# Power.net
KiCad netlist of a schematic drawn in Altium Designer
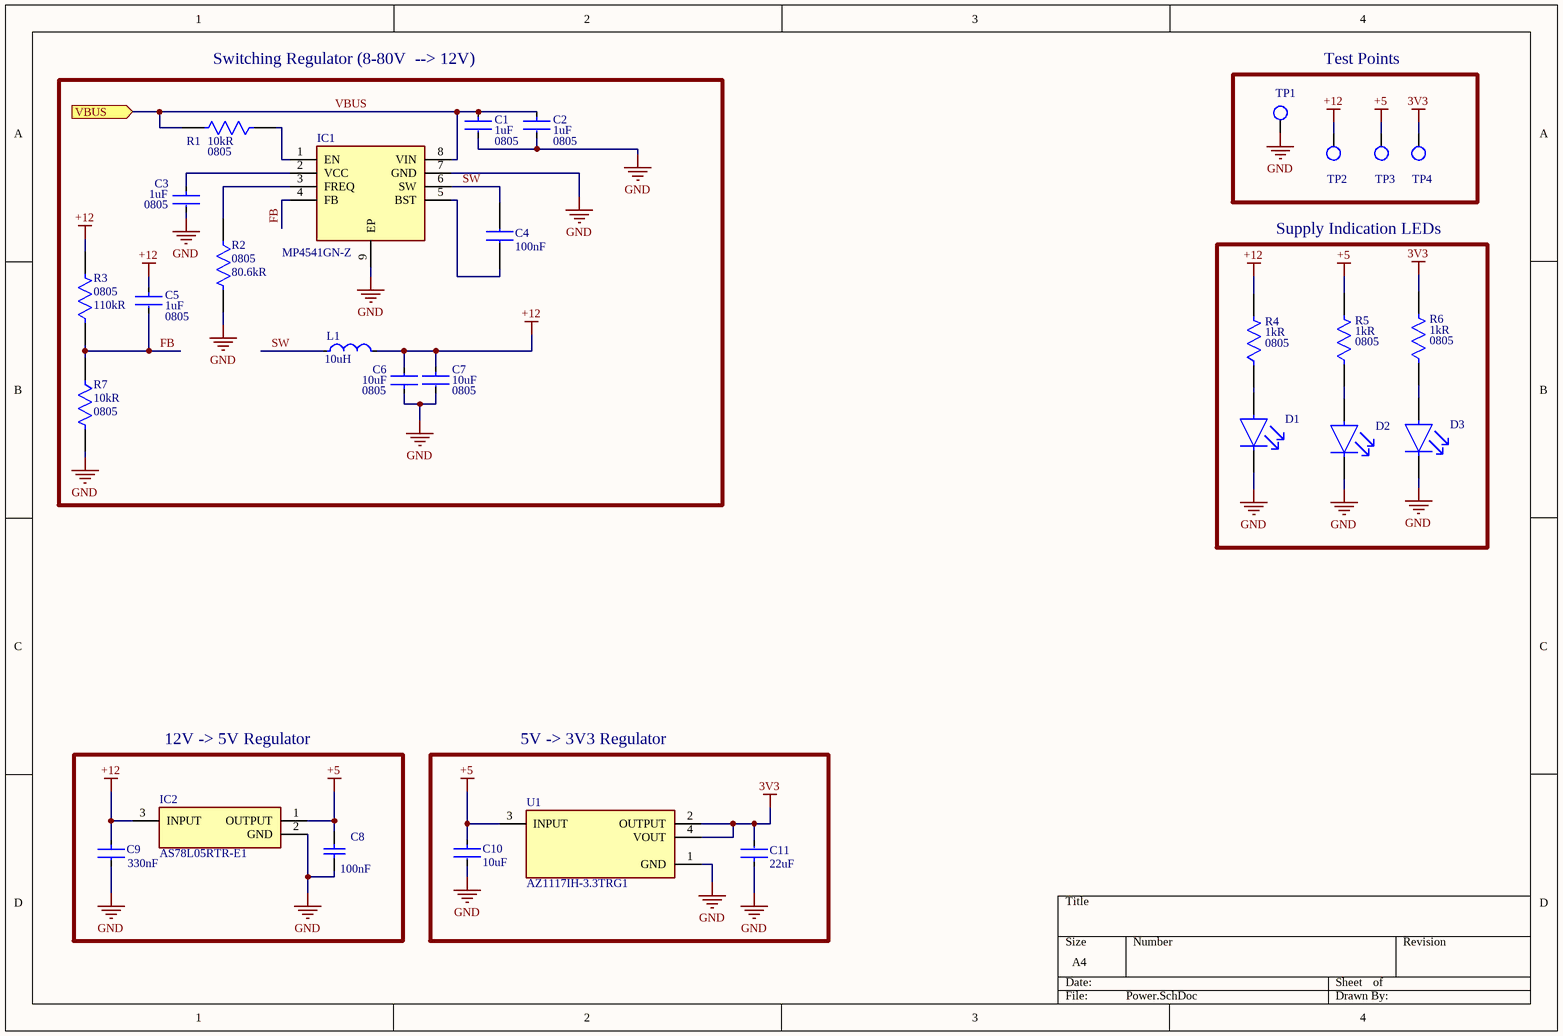
[diagram p0: Power.SchDoc]

(export (version "E")
  (design (tool "Eeschema 10.0.6"))
  (components
    (comp (ref "C1")
      (value "885012207078")
      (footprint "FP-885012207078-MFG")
      (description "CAP CER 1UF 25V X7R 0805")
      (fields
        (field (name "CAPACITANCE") "1uF")
        (field (name "CASE CODE (IMPERIAL)") "0805")
        (field (name "TOLERANCE") "10%")
      )
      (libsource (lib "Altium Content Vault") (part "b4654b650e69147ec39a6b967a45e02"))
    )
    (comp (ref "C2")
      (value "885012207078")
      (footprint "FP-885012207078-MFG")
      (description "CAP CER 1UF 25V X7R 0805")
      (fields
        (field (name "CAPACITANCE") "1uF")
        (field (name "CASE CODE (IMPERIAL)") "0805")
        (field (name "TOLERANCE") "10%")
      )
      (libsource (lib "Altium Content Vault") (part "b4654b650e69147ec39a6b967a45e02"))
    )
    (comp (ref "C3")
      (value "885012207078")
      (footprint "FP-885012207078-MFG")
      (description "CAP CER 1UF 25V X7R 0805")
      (fields
        (field (name "CAPACITANCE") "1uF")
        (field (name "CASE CODE (IMPERIAL)") "0805")
        (field (name "TOLERANCE") "10%")
      )
      (libsource (lib "Altium Content Vault") (part "b4654b650e69147ec39a6b967a45e02"))
    )
    (comp (ref "C4")
      (value "C0805C104K1RACAUTO7210")
      (footprint "C0805")
      (description "Capacitor")
      (fields (field (name "MOUSER PART NUMBER") "80-C0805C104K1RAUTLR") (field (name "CAPACITANCE") "100nF"))
      (libsource (lib "WPT_Transmitter_lib") (part "C0805C104K1RACAUTO7210"))
    )
    (comp (ref "C5")
      (value "885012207078")
      (footprint "FP-885012207078-MFG")
      (description "CAP CER 1UF 25V X7R 0805")
      (fields
        (field (name "CAPACITANCE") "1uF")
        (field (name "CASE CODE (IMPERIAL)") "0805")
        (field (name "TOLERANCE") "10%")
      )
      (libsource (lib "Altium Content Vault") (part "b4654b650e69147ec39a6b967a45e02"))
    )
    (comp (ref "C6")
      (value "CL21A106KOQNNNG")
      (footprint "FP-CL21-IPC_C")
      (description "CL21 Series 0805 10uF 16V ±10% Tolerance X5R Multilayer Ceramic Chip Capacitor")
      (fields
        (field (name "CAPACITANCE") "10uF")
        (field (name "TOLERANCE") "10%")
        (field (name "CASE/PACKAGE") "0805")
        (field (name "VOLTAGE") "16V")
      )
      (libsource (lib "Altium Content Vault") (part "b4654b650e69147ec39a6b967a45e02"))
    )
    (comp (ref "C7")
      (value "CL21A106KOQNNNG")
      (footprint "FP-CL21-IPC_C")
      (description "CL21 Series 0805 10uF 16V ±10% Tolerance X5R Multilayer Ceramic Chip Capacitor")
      (fields
        (field (name "CAPACITANCE") "10uF")
        (field (name "TOLERANCE") "10%")
        (field (name "CASE/PACKAGE") "0805")
        (field (name "VOLTAGE") "16V")
      )
      (libsource (lib "Altium Content Vault") (part "b4654b650e69147ec39a6b967a45e02"))
    )
    (comp (ref "C8")
      (value "08055D104KAT2A")
      (footprint "CAPC2013X140X50ML20T25")
      (fields (field (name "MANUFACTURER") "AVX Interconnect / Elco") (field (name "CAPACITANCE") "100nF"))
      (libsource (lib "Altium Content Vault") (part "CAP"))
    )
    (comp (ref "C9")
      (value "CL21B334KBFNNNE")
      (footprint "FP-CL21-F-IPC_C")
      (description "CAP CER 0.33UF 50V X7R 0805")
      (fields
        (field (name "CAPACITANCE") "330nF")
        (field (name "MANUFACTURER") "Samsung Electro-Mechanics")
        (field (name "OCTOPART") "https://octopart.com/cl21b334kbfnnne-samsung-9287149")
      )
      (libsource (lib "Altium Content Vault") (part "11868f565c42a9108669ba33697ecf6"))
    )
    (comp (ref "C10")
      (value "CL21A106KOQNNNE")
      (footprint "FP-CL21-IPC_B")
      (description "CL21 Series 0805 10uF 16V ±10% Tolerance X5R Multilayer Ceramic Chip Capacitor")
      (fields
        (field (name "VOLTAGE") "16V")
        (field (name "CAPACITANCE") "10uF")
        (field (name "TOLERANCE") "10%")
      )
      (libsource (lib "Altium Content Vault") (part "b4654b650e69147ec39a6b967a45e02"))
    )
    (comp (ref "C11")
      (value "CL21A226MQQNNNG")
      (footprint "FP-CL21-IPC_B")
      (description "CL21 Series 0805 22uF 6.3V ±20% Tolerance X5R Multilayer Ceramic Chip Capacitor")
      (fields
        (field (name "TOLERANCE") "20%")
        (field (name "CAPACITANCE") "22uF")
        (field (name "VOLTAGE") "6.3V")
      )
      (libsource (lib "Altium Content Vault") (part "b4654b650e69147ec39a6b967a45e02"))
    )
    (comp (ref "D1")
      (value "12V")
      (footprint "FP-150060VS75000-MFG")
      (description "LED GREEN CLEAR 0603 SMD")
      (libsource (lib "Altium Content Vault") (part "8706943c75ba83719d021d2fdc84c58"))
    )
    (comp (ref "D2")
      (value "5V")
      (footprint "FP-150060VS75000-MFG")
      (description "LED GREEN CLEAR 0603 SMD")
      (libsource (lib "Altium Content Vault") (part "8706943c75ba83719d021d2fdc84c58"))
    )
    (comp (ref "D3")
      (value "3V3")
      (footprint "FP-150060VS75000-MFG")
      (description "LED GREEN CLEAR 0603 SMD")
      (libsource (lib "Altium Content Vault") (part "8706943c75ba83719d021d2fdc84c58"))
    )
    (comp (ref "IC1")
      (value "MP4541GN-Z")
      (footprint "WPT_Transmitter_lib:SOIC127P600X170-9N")
      (description "Integrated Circuit")
      (fields (field (name "MOUSER PART NUMBER") "946-MP4541GN-Z"))
      (libsource (lib "WPT_Transmitter_lib") (part "MP4541GN-Z"))
    )
    (comp (ref "IC2")
      (value "AS78L05RTR-E1")
      (footprint "WPT_Transmitter_lib:DIODES_SOT-89")
      (description "Integrated Circuit")
      (fields (field (name "MOUSER PART NUMBER") "621-AS78L05RTR-E1"))
      (libsource (lib "WPT_Transmitter_lib") (part "AS78L05RTR-E1"))
    )
    (comp (ref "L1")
      (value "LBR2518T100K")
      (footprint "FP-LB2518-1_8-0_2-IPC_A")
      (description "SMD Inductors 10uH ±10% 0.235A 0.247Ω 1007")
      (fields (field (name "INDUCTANCE") "10uH") (field (name "TOLERANCE") "10%"))
      (libsource (lib "Altium Content Vault") (part "725321dda6339637d4d059423bc1c3c"))
    )
    (comp (ref "R1")
      (value "RMCF0805JT10K0")
      (footprint "FP-RMCF0805-IPC_A")
      (description "10kΩ ±5% 0.125W 0805 Thick Film Chip Resistor AEC-Q200 compliant")
      (fields
        (field (name "RESISTANCE") "10kR")
        (field (name "CASE CODE (IMPERIAL)") "0805")
        (field (name "TOLERANCE") "5%")
      )
      (libsource (lib "Altium Content Vault") (part "1029c3af85768c4190bb7ad29bc67b5"))
    )
    (comp (ref "R2")
      (value "CRCW080580K6FKEA")
      (footprint "FP-CRCW0805-e3-IPC_A")
      (description "RES Thick Film, 80.6kΩ, 1%, 0.125W, 100ppm/°C, 0805")
      (fields
        (field (name "TOLERANCE") "1%")
        (field (name "CASE/PACKAGE") "0805")
        (field (name "RESISTANCE") "80.6kR")
      )
      (libsource (lib "Altium Content Vault") (part "1029c3af85768c4190bb7ad29bc67b5"))
    )
    (comp (ref "R3")
      (value "RMCF0805FT110K")
      (footprint "FP-RMCF0805-IPC_C")
      (description "110kΩ ±1% 0.125W 0805 Thick Film Chip Resistor AEC-Q200 compliant")
      (fields
        (field (name "SIZE CODE") "0805")
        (field (name "TOLERANCE") "1%")
        (field (name "RESISTANCE") "110kR")
      )
      (libsource (lib "Altium Content Vault") (part "1029c3af85768c4190bb7ad29bc67b5"))
    )
    (comp (ref "R4")
      (value "RNCP0805FTD1K00")
      (footprint "FP-RNCP0805-MFG")
      (description "1kΩ ±1% 0.25W 0805 High Power Anti-Sulfur Thin Film Chip Resistor")
      (fields
        (field (name "RESISTANCE") "1kR")
        (field (name "SIZE CODE") "0805")
        (field (name "TOLERANCE") "1%")
      )
      (libsource (lib "Altium Content Vault") (part "1029c3af85768c4190bb7ad29bc67b5"))
    )
    (comp (ref "R5")
      (value "RNCP0805FTD1K00")
      (footprint "FP-RNCP0805-MFG")
      (description "1kΩ ±1% 0.25W 0805 High Power Anti-Sulfur Thin Film Chip Resistor")
      (fields
        (field (name "RESISTANCE") "1kR")
        (field (name "SIZE CODE") "0805")
        (field (name "TOLERANCE") "1%")
      )
      (libsource (lib "Altium Content Vault") (part "1029c3af85768c4190bb7ad29bc67b5"))
    )
    (comp (ref "R6")
      (value "RNCP0805FTD1K00")
      (footprint "FP-RNCP0805-MFG")
      (description "1kΩ ±1% 0.25W 0805 High Power Anti-Sulfur Thin Film Chip Resistor")
      (fields
        (field (name "RESISTANCE") "1kR")
        (field (name "SIZE CODE") "0805")
        (field (name "TOLERANCE") "1%")
      )
      (libsource (lib "Altium Content Vault") (part "1029c3af85768c4190bb7ad29bc67b5"))
    )
    (comp (ref "R7")
      (value "RMCF0805JT10K0")
      (footprint "FP-RMCF0805-IPC_A")
      (description "10kΩ ±5% 0.125W 0805 Thick Film Chip Resistor AEC-Q200 compliant")
      (fields
        (field (name "RESISTANCE") "10kR")
        (field (name "CASE CODE (IMPERIAL)") "0805")
        (field (name "TOLERANCE") "5%")
      )
      (libsource (lib "Altium Content Vault") (part "1029c3af85768c4190bb7ad29bc67b5"))
    )
    (comp (ref "TP1")
      (value "GND")
      (footprint "TESTPOINT_LOOP")
      (description "PC TEST POINT MINIATURE WHITE")
      (libsource (lib "Connectors and Headers") (part "TESTPOINT_LOOP"))
    )
    (comp (ref "TP2")
      (value "12V")
      (footprint "TESTPOINT_LOOP")
      (description "PC TEST POINT MINIATURE WHITE")
      (libsource (lib "Connectors and Headers") (part "TESTPOINT_LOOP"))
    )
    (comp (ref "TP3")
      (value "5V")
      (footprint "TESTPOINT_LOOP")
      (description "PC TEST POINT MINIATURE WHITE")
      (libsource (lib "Connectors and Headers") (part "TESTPOINT_LOOP"))
    )
    (comp (ref "TP4")
      (value "3V3")
      (footprint "TESTPOINT_LOOP")
      (description "PC TEST POINT MINIATURE WHITE")
      (libsource (lib "Connectors and Headers") (part "TESTPOINT_LOOP"))
    )
    (comp (ref "U1")
      (value "AZ1117IH-3.3TRG1")
      (footprint "FP-SOT223-IPC_B")
      (description "IC REG LINEAR 3.3V 1A SOT223")
      (libsource (lib "Altium Content Vault") (part "3c8a0cc3f7d1fafcf032f21e1bb5f65"))
    )
  )
  (nets
    (net (code "1") (name "+5") (class "Default")
      (node (ref "C10") (pin "1") (pinfunction "1_1") (pintype "passive"))
      (node (ref "C8") (pin "2") (pinfunction "2_2") (pintype "passive"))
      (node (ref "IC2") (pin "1") (pinfunction "OUTPUT_1") (pintype "passive"))
      (node (ref "R5") (pin "2") (pinfunction "2_2") (pintype "passive"))
      (node (ref "TP3") (pin "1") (pintype "passive"))
      (node (ref "U1") (pin "3") (pinfunction "INPUT_3") (pintype "power_in"))
    )
    (net (code "2") (name "+12") (class "Default")
      (node (ref "C5") (pin "1") (pinfunction "1_1") (pintype "passive"))
      (node (ref "C6") (pin "2") (pinfunction "2_2") (pintype "passive"))
      (node (ref "C7") (pin "1") (pinfunction "1_1") (pintype "passive"))
      (node (ref "C9") (pin "1") (pinfunction "1_1") (pintype "passive"))
      (node (ref "IC2") (pin "3") (pinfunction "INPUT_3") (pintype "passive"))
      (node (ref "L1") (pin "2") (pinfunction "2_2") (pintype "passive"))
      (node (ref "R3") (pin "2") (pinfunction "2_2") (pintype "passive"))
      (node (ref "R4") (pin "2") (pinfunction "2_2") (pintype "passive"))
      (node (ref "TP2") (pin "1") (pintype "passive"))
    )
    (net (code "3") (name "/FB") (class "Default")
      (node (ref "C5") (pin "2") (pinfunction "2_2") (pintype "passive"))
      (node (ref "IC1") (pin "4") (pinfunction "FB_4") (pintype "passive"))
      (node (ref "R3") (pin "1") (pinfunction "1_1") (pintype "passive"))
      (node (ref "R7") (pin "1") (pinfunction "1_1") (pintype "passive"))
    )
    (net (code "4") (name "/SW") (class "Default")
      (node (ref "C4") (pin "2") (pinfunction "2_2") (pintype "passive"))
      (node (ref "IC1") (pin "6") (pinfunction "SW_6") (pintype "passive"))
      (node (ref "L1") (pin "1") (pinfunction "1_1") (pintype "passive"))
    )
    (net (code "5") (name "/VBUS") (class "Default")
      (node (ref "C1") (pin "1") (pinfunction "1_1") (pintype "passive"))
      (node (ref "C2") (pin "1") (pinfunction "1_1") (pintype "passive"))
      (node (ref "IC1") (pin "8") (pinfunction "VIN_8") (pintype "passive"))
      (node (ref "R1") (pin "2") (pinfunction "2_2") (pintype "passive"))
    )
    (net (code "6") (name "3V3") (class "Default")
      (node (ref "C11") (pin "2") (pinfunction "2_2") (pintype "passive"))
      (node (ref "R6") (pin "2") (pinfunction "2_2") (pintype "passive"))
      (node (ref "TP4") (pin "1") (pintype "passive"))
      (node (ref "U1") (pin "2") (pinfunction "OUTPUT_2") (pintype "power_in"))
      (node (ref "U1") (pin "4") (pinfunction "VOUT_4") (pintype "power_in"))
    )
    (net (code "7") (name "GND") (class "Default")
      (node (ref "C1") (pin "2") (pinfunction "2_2") (pintype "passive"))
      (node (ref "C10") (pin "2") (pinfunction "2_2") (pintype "passive"))
      (node (ref "C11") (pin "1") (pinfunction "1_1") (pintype "passive"))
      (node (ref "C2") (pin "2") (pinfunction "2_2") (pintype "passive"))
      (node (ref "C3") (pin "2") (pinfunction "2_2") (pintype "passive"))
      (node (ref "C6") (pin "1") (pinfunction "1_1") (pintype "passive"))
      (node (ref "C7") (pin "2") (pinfunction "2_2") (pintype "passive"))
      (node (ref "C8") (pin "1") (pinfunction "1_1") (pintype "passive"))
      (node (ref "C9") (pin "2") (pinfunction "2_2") (pintype "passive"))
      (node (ref "D1") (pin "1") (pinfunction "C_1") (pintype "passive"))
      (node (ref "D2") (pin "1") (pinfunction "C_1") (pintype "passive"))
      (node (ref "D3") (pin "1") (pinfunction "C_1") (pintype "passive"))
      (node (ref "IC1") (pin "7") (pinfunction "GND_7") (pintype "passive"))
      (node (ref "IC1") (pin "9") (pinfunction "EP_9") (pintype "passive"))
      (node (ref "IC2") (pin "2") (pinfunction "GND_2") (pintype "passive"))
      (node (ref "R2") (pin "2") (pinfunction "2_2") (pintype "passive"))
      (node (ref "R7") (pin "2") (pinfunction "2_2") (pintype "passive"))
      (node (ref "TP1") (pin "1") (pintype "passive"))
      (node (ref "U1") (pin "1") (pinfunction "GND_1") (pintype "power_in"))
    )
    (net (code "8") (name "Net-(D1-A)") (class "Default")
      (node (ref "D1") (pin "2") (pinfunction "A_2") (pintype "passive"))
      (node (ref "R4") (pin "1") (pinfunction "1_1") (pintype "passive"))
    )
    (net (code "9") (name "Net-(D2-A)") (class "Default")
      (node (ref "D2") (pin "2") (pinfunction "A_2") (pintype "passive"))
      (node (ref "R5") (pin "1") (pinfunction "1_1") (pintype "passive"))
    )
    (net (code "10") (name "Net-(D3-A)") (class "Default")
      (node (ref "D3") (pin "2") (pinfunction "A_2") (pintype "passive"))
      (node (ref "R6") (pin "1") (pinfunction "1_1") (pintype "passive"))
    )
    (net (code "11") (name "Net-(IC1-BST)") (class "Default")
      (node (ref "C4") (pin "1") (pinfunction "1_1") (pintype "passive"))
      (node (ref "IC1") (pin "5") (pinfunction "BST_5") (pintype "passive"))
    )
    (net (code "12") (name "Net-(IC1-EN)") (class "Default")
      (node (ref "IC1") (pin "1") (pinfunction "EN_1") (pintype "passive"))
      (node (ref "R1") (pin "1") (pinfunction "1_1") (pintype "passive"))
    )
    (net (code "13") (name "Net-(IC1-FREQ)") (class "Default")
      (node (ref "IC1") (pin "3") (pinfunction "FREQ_3") (pintype "passive"))
      (node (ref "R2") (pin "1") (pinfunction "1_1") (pintype "passive"))
    )
    (net (code "14") (name "Net-(IC1-VCC)") (class "Default")
      (node (ref "C3") (pin "1") (pinfunction "1_1") (pintype "passive"))
      (node (ref "IC1") (pin "2") (pinfunction "VCC_2") (pintype "passive"))
    )
  )
)
